# sum-mixer.net
KiCad netlist of a schematic drawn in EAGLE
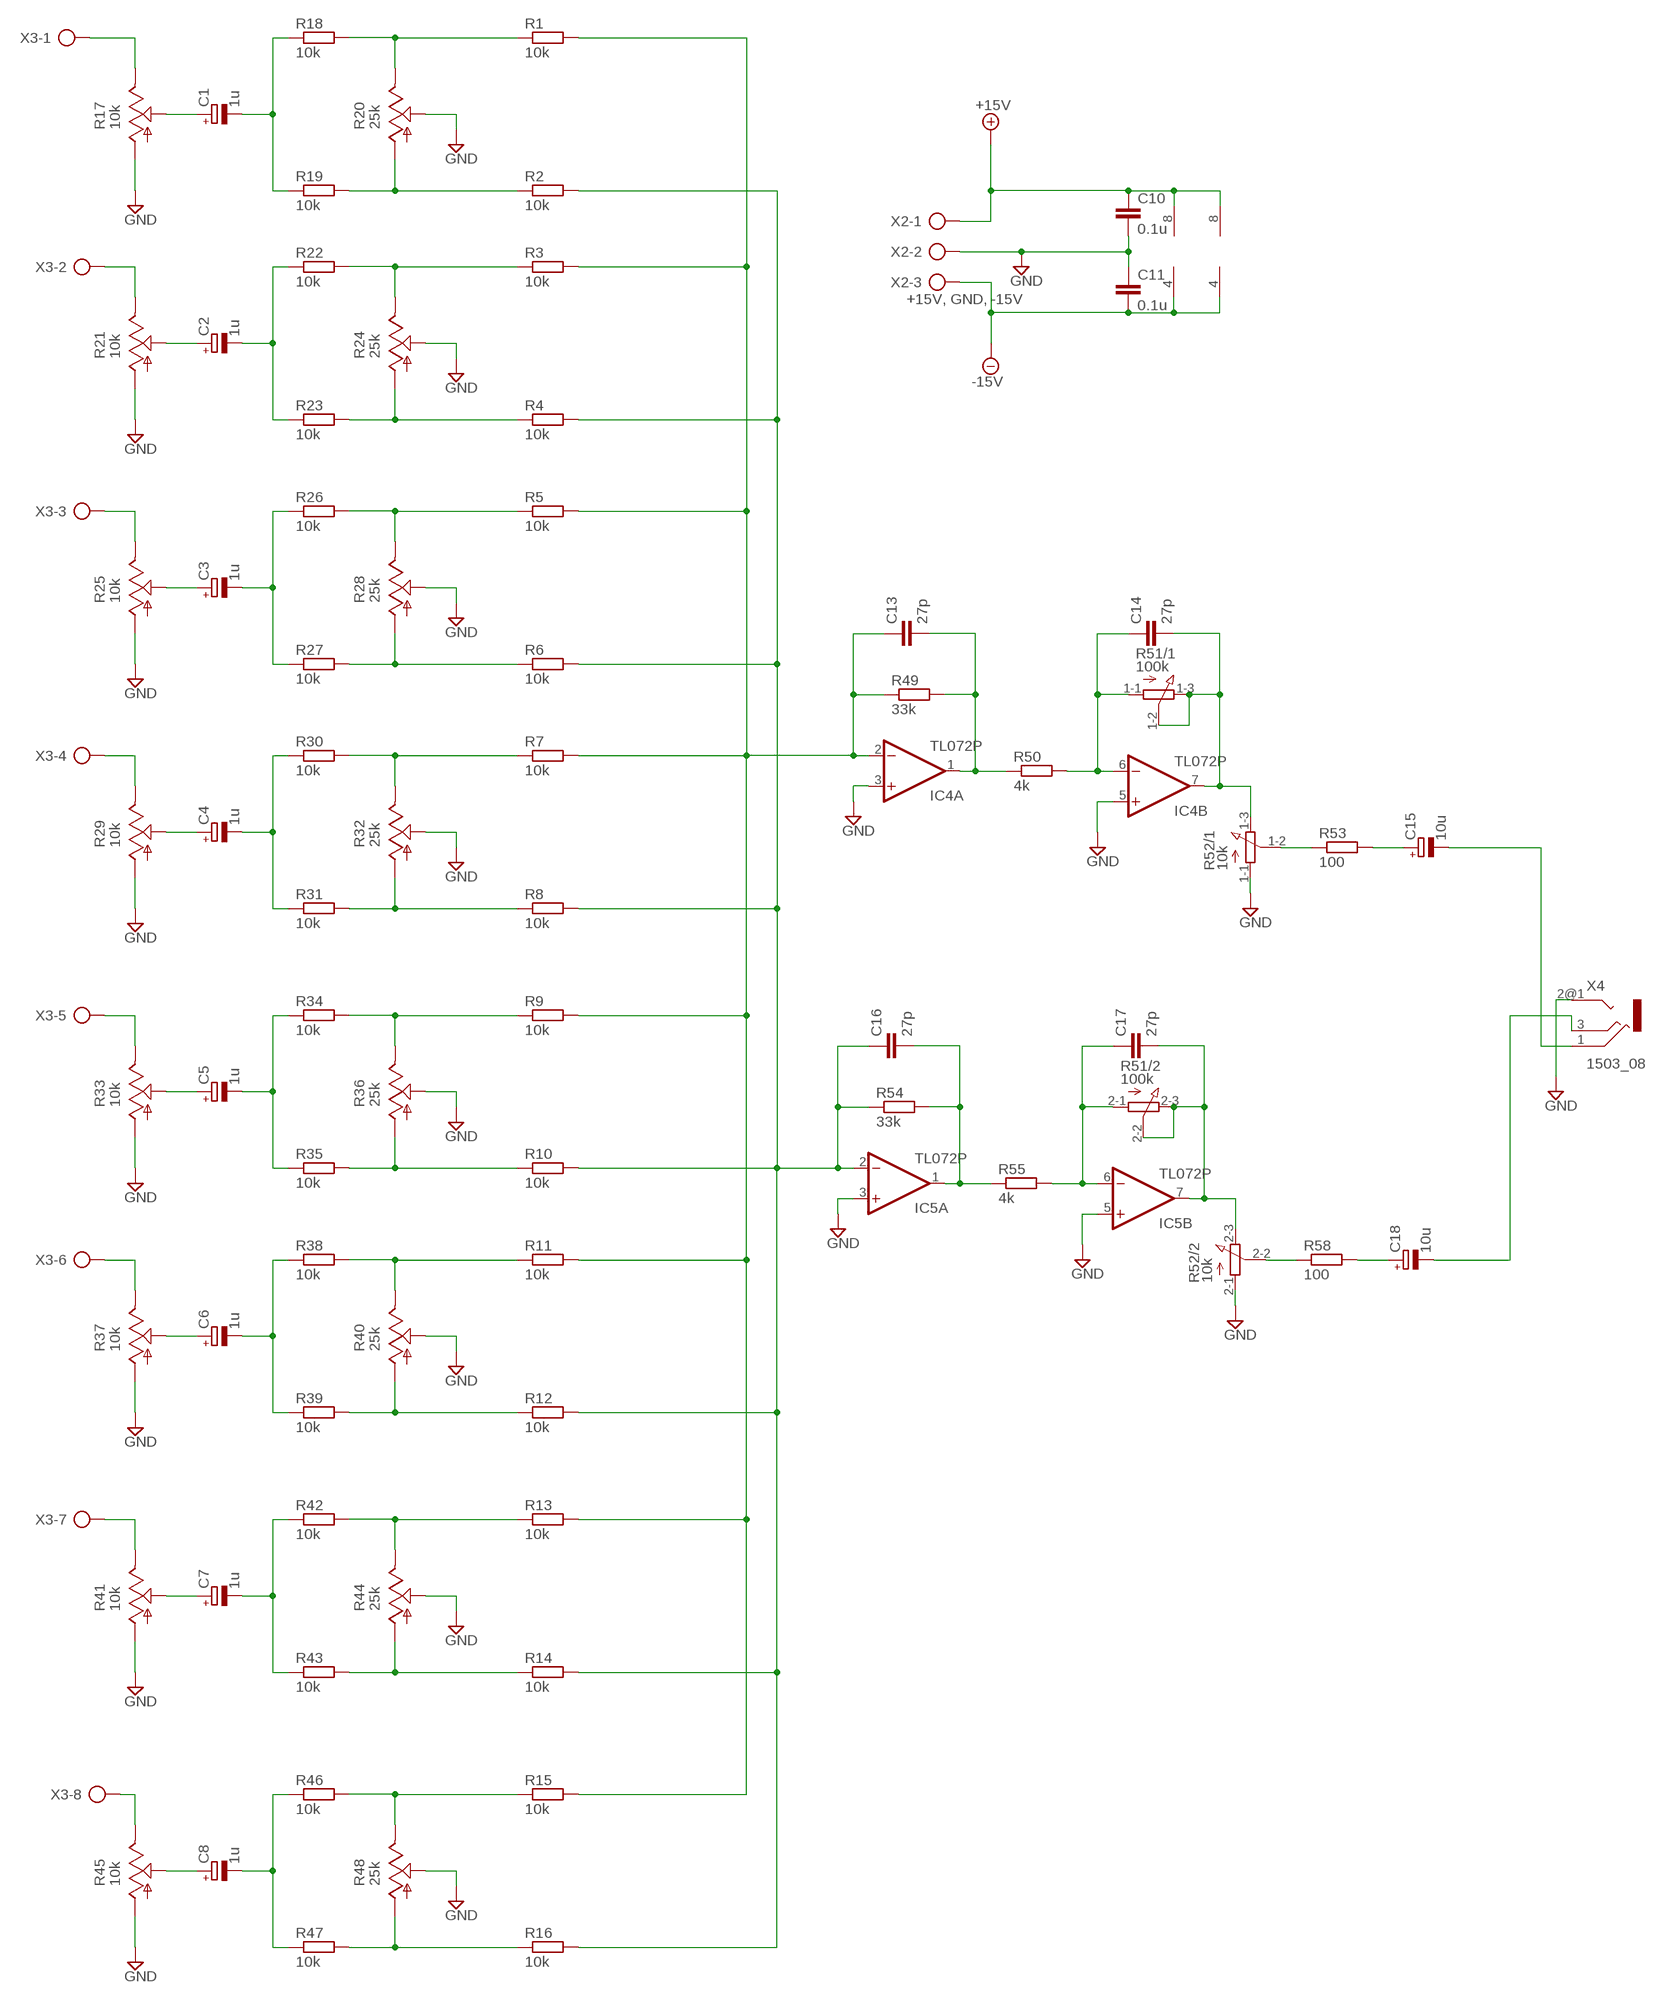
[diagram p0: schematic, sheet 1]

(export (version "E")
  (design (tool "Eeschema 10.0.6"))
  (components
    (comp (ref "C1")
      (value "1u")
      (footprint "eagle-import:E5-6")
      (libsource (lib "eagle-import") (part "CPOL-EUE5-6"))
    )
    (comp (ref "C2")
      (value "1u")
      (footprint "eagle-import:E5-6")
      (libsource (lib "eagle-import") (part "CPOL-EUE5-6"))
    )
    (comp (ref "C3")
      (value "1u")
      (footprint "eagle-import:E5-6")
      (libsource (lib "eagle-import") (part "CPOL-EUE5-6"))
    )
    (comp (ref "C4")
      (value "1u")
      (footprint "eagle-import:E5-6")
      (libsource (lib "eagle-import") (part "CPOL-EUE5-6"))
    )
    (comp (ref "C5")
      (value "1u")
      (footprint "eagle-import:E5-6")
      (libsource (lib "eagle-import") (part "CPOL-EUE5-6"))
    )
    (comp (ref "C6")
      (value "1u")
      (footprint "eagle-import:E5-6")
      (libsource (lib "eagle-import") (part "CPOL-EUE5-6"))
    )
    (comp (ref "C7")
      (value "1u")
      (footprint "eagle-import:E5-6")
      (libsource (lib "eagle-import") (part "CPOL-EUE5-6"))
    )
    (comp (ref "C8")
      (value "1u")
      (footprint "eagle-import:E5-6")
      (libsource (lib "eagle-import") (part "CPOL-EUE5-6"))
    )
    (comp (ref "C10")
      (value "0.1u")
      (footprint "eagle-import:C075-042X103")
      (libsource (lib "eagle-import") (part "C-EU075-042X103"))
    )
    (comp (ref "C11")
      (value "0.1u")
      (footprint "eagle-import:C075-042X103")
      (libsource (lib "eagle-import") (part "C-EU075-042X103"))
    )
    (comp (ref "C13")
      (value "27p")
      (footprint "eagle-import:C025-024X044")
      (libsource (lib "eagle-import") (part "C-EU025-024X044"))
    )
    (comp (ref "C14")
      (value "27p")
      (footprint "eagle-import:C025-024X044")
      (libsource (lib "eagle-import") (part "C-EU025-024X044"))
    )
    (comp (ref "C15")
      (value "10u")
      (footprint "eagle-import:E5-6")
      (libsource (lib "eagle-import") (part "CPOL-EUE5-6"))
    )
    (comp (ref "C16")
      (value "27p")
      (footprint "eagle-import:C025-024X044")
      (libsource (lib "eagle-import") (part "C-EU025-024X044"))
    )
    (comp (ref "C17")
      (value "27p")
      (footprint "eagle-import:C025-024X044")
      (libsource (lib "eagle-import") (part "C-EU025-024X044"))
    )
    (comp (ref "C18")
      (value "10u")
      (footprint "eagle-import:E5-6")
      (libsource (lib "eagle-import") (part "CPOL-EUE5-6"))
    )
    (comp (ref "IC4")
      (value "TL072P")
      (footprint "eagle-import:DIL08")
      (libsource (lib "eagle-import") (part "TL072P"))
    )
    (comp (ref "IC5")
      (value "TL072P")
      (footprint "eagle-import:DIL08")
      (libsource (lib "eagle-import") (part "TL072P"))
    )
    (comp (ref "R1")
      (value "10k")
      (footprint "eagle-import:0207_5V")
      (libsource (lib "eagle-import") (part "R-EU_0207/5V"))
    )
    (comp (ref "R2")
      (value "10k")
      (footprint "eagle-import:0207_5V")
      (libsource (lib "eagle-import") (part "R-EU_0207/5V"))
    )
    (comp (ref "R3")
      (value "10k")
      (footprint "eagle-import:0207_5V")
      (libsource (lib "eagle-import") (part "R-EU_0207/5V"))
    )
    (comp (ref "R4")
      (value "10k")
      (footprint "eagle-import:0207_5V")
      (libsource (lib "eagle-import") (part "R-EU_0207/5V"))
    )
    (comp (ref "R5")
      (value "10k")
      (footprint "eagle-import:0207_5V")
      (libsource (lib "eagle-import") (part "R-EU_0207/5V"))
    )
    (comp (ref "R6")
      (value "10k")
      (footprint "eagle-import:0207_5V")
      (libsource (lib "eagle-import") (part "R-EU_0207/5V"))
    )
    (comp (ref "R7")
      (value "10k")
      (footprint "eagle-import:0207_5V")
      (libsource (lib "eagle-import") (part "R-EU_0207/5V"))
    )
    (comp (ref "R8")
      (value "10k")
      (footprint "eagle-import:0207_5V")
      (libsource (lib "eagle-import") (part "R-EU_0207/5V"))
    )
    (comp (ref "R9")
      (value "10k")
      (footprint "eagle-import:0207_5V")
      (libsource (lib "eagle-import") (part "R-EU_0207/5V"))
    )
    (comp (ref "R10")
      (value "10k")
      (footprint "eagle-import:0207_5V")
      (libsource (lib "eagle-import") (part "R-EU_0207/5V"))
    )
    (comp (ref "R11")
      (value "10k")
      (footprint "eagle-import:0207_5V")
      (libsource (lib "eagle-import") (part "R-EU_0207/5V"))
    )
    (comp (ref "R12")
      (value "10k")
      (footprint "eagle-import:0207_5V")
      (libsource (lib "eagle-import") (part "R-EU_0207/5V"))
    )
    (comp (ref "R13")
      (value "10k")
      (footprint "eagle-import:0207_5V")
      (libsource (lib "eagle-import") (part "R-EU_0207/5V"))
    )
    (comp (ref "R14")
      (value "10k")
      (footprint "eagle-import:0207_5V")
      (libsource (lib "eagle-import") (part "R-EU_0207/5V"))
    )
    (comp (ref "R15")
      (value "10k")
      (footprint "eagle-import:0207_5V")
      (libsource (lib "eagle-import") (part "R-EU_0207/5V"))
    )
    (comp (ref "R16")
      (value "10k")
      (footprint "eagle-import:0207_5V")
      (libsource (lib "eagle-import") (part "R-EU_0207/5V"))
    )
    (comp (ref "R17")
      (value "10k")
      (footprint "eagle-import:B25P")
      (libsource (lib "eagle-import") (part "TRIM_US-B25P"))
    )
    (comp (ref "R18")
      (value "10k")
      (footprint "eagle-import:0207_5V")
      (libsource (lib "eagle-import") (part "R-EU_0207/5V"))
    )
    (comp (ref "R19")
      (value "10k")
      (footprint "eagle-import:0207_5V")
      (libsource (lib "eagle-import") (part "R-EU_0207/5V"))
    )
    (comp (ref "R20")
      (value "25k")
      (footprint "eagle-import:B25P")
      (libsource (lib "eagle-import") (part "TRIM_US-B25P"))
    )
    (comp (ref "R21")
      (value "10k")
      (footprint "eagle-import:B25P")
      (libsource (lib "eagle-import") (part "TRIM_US-B25P"))
    )
    (comp (ref "R22")
      (value "10k")
      (footprint "eagle-import:0207_5V")
      (libsource (lib "eagle-import") (part "R-EU_0207/5V"))
    )
    (comp (ref "R23")
      (value "10k")
      (footprint "eagle-import:0207_5V")
      (libsource (lib "eagle-import") (part "R-EU_0207/5V"))
    )
    (comp (ref "R24")
      (value "25k")
      (footprint "eagle-import:B25P")
      (libsource (lib "eagle-import") (part "TRIM_US-B25P"))
    )
    (comp (ref "R25")
      (value "10k")
      (footprint "eagle-import:B25P")
      (libsource (lib "eagle-import") (part "TRIM_US-B25P"))
    )
    (comp (ref "R26")
      (value "10k")
      (footprint "eagle-import:0207_5V")
      (libsource (lib "eagle-import") (part "R-EU_0207/5V"))
    )
    (comp (ref "R27")
      (value "10k")
      (footprint "eagle-import:0207_5V")
      (libsource (lib "eagle-import") (part "R-EU_0207/5V"))
    )
    (comp (ref "R28")
      (value "25k")
      (footprint "eagle-import:B25P")
      (libsource (lib "eagle-import") (part "TRIM_US-B25P"))
    )
    (comp (ref "R29")
      (value "10k")
      (footprint "eagle-import:B25P")
      (libsource (lib "eagle-import") (part "TRIM_US-B25P"))
    )
    (comp (ref "R30")
      (value "10k")
      (footprint "eagle-import:0207_5V")
      (libsource (lib "eagle-import") (part "R-EU_0207/5V"))
    )
    (comp (ref "R31")
      (value "10k")
      (footprint "eagle-import:0207_5V")
      (libsource (lib "eagle-import") (part "R-EU_0207/5V"))
    )
    (comp (ref "R32")
      (value "25k")
      (footprint "eagle-import:B25P")
      (libsource (lib "eagle-import") (part "TRIM_US-B25P"))
    )
    (comp (ref "R33")
      (value "10k")
      (footprint "eagle-import:B25P")
      (libsource (lib "eagle-import") (part "TRIM_US-B25P"))
    )
    (comp (ref "R34")
      (value "10k")
      (footprint "eagle-import:0207_5V")
      (libsource (lib "eagle-import") (part "R-EU_0207/5V"))
    )
    (comp (ref "R35")
      (value "10k")
      (footprint "eagle-import:0207_5V")
      (libsource (lib "eagle-import") (part "R-EU_0207/5V"))
    )
    (comp (ref "R36")
      (value "25k")
      (footprint "eagle-import:B25P")
      (libsource (lib "eagle-import") (part "TRIM_US-B25P"))
    )
    (comp (ref "R37")
      (value "10k")
      (footprint "eagle-import:B25P")
      (libsource (lib "eagle-import") (part "TRIM_US-B25P"))
    )
    (comp (ref "R38")
      (value "10k")
      (footprint "eagle-import:0207_5V")
      (libsource (lib "eagle-import") (part "R-EU_0207/5V"))
    )
    (comp (ref "R39")
      (value "10k")
      (footprint "eagle-import:0207_5V")
      (libsource (lib "eagle-import") (part "R-EU_0207/5V"))
    )
    (comp (ref "R40")
      (value "25k")
      (footprint "eagle-import:B25P")
      (libsource (lib "eagle-import") (part "TRIM_US-B25P"))
    )
    (comp (ref "R41")
      (value "10k")
      (footprint "eagle-import:B25P")
      (libsource (lib "eagle-import") (part "TRIM_US-B25P"))
    )
    (comp (ref "R42")
      (value "10k")
      (footprint "eagle-import:0207_5V")
      (libsource (lib "eagle-import") (part "R-EU_0207/5V"))
    )
    (comp (ref "R43")
      (value "10k")
      (footprint "eagle-import:0207_5V")
      (libsource (lib "eagle-import") (part "R-EU_0207/5V"))
    )
    (comp (ref "R44")
      (value "25k")
      (footprint "eagle-import:B25P")
      (libsource (lib "eagle-import") (part "TRIM_US-B25P"))
    )
    (comp (ref "R45")
      (value "10k")
      (footprint "eagle-import:B25P")
      (libsource (lib "eagle-import") (part "TRIM_US-B25P"))
    )
    (comp (ref "R46")
      (value "10k")
      (footprint "eagle-import:0207_5V")
      (libsource (lib "eagle-import") (part "R-EU_0207/5V"))
    )
    (comp (ref "R47")
      (value "10k")
      (footprint "eagle-import:0207_5V")
      (libsource (lib "eagle-import") (part "R-EU_0207/5V"))
    )
    (comp (ref "R48")
      (value "25k")
      (footprint "eagle-import:B25P")
      (libsource (lib "eagle-import") (part "TRIM_US-B25P"))
    )
    (comp (ref "R49")
      (value "33k")
      (footprint "eagle-import:0207_5V")
      (libsource (lib "eagle-import") (part "R-EU_0207/5V"))
    )
    (comp (ref "R50")
      (value "4k")
      (footprint "eagle-import:0207_5V")
      (libsource (lib "eagle-import") (part "R-EU_0207/5V"))
    )
    (comp (ref "R51")
      (value "100k")
      (footprint "eagle-import:3RP_1610G")
      (libsource (lib "eagle-import") (part "3RP/1610G"))
    )
    (comp (ref "R52")
      (value "10k")
      (footprint "eagle-import:3RP_1610G")
      (libsource (lib "eagle-import") (part "3RP/1610G"))
    )
    (comp (ref "R53")
      (value "100")
      (footprint "eagle-import:0207_5V")
      (libsource (lib "eagle-import") (part "R-EU_0207/5V"))
    )
    (comp (ref "R54")
      (value "33k")
      (footprint "eagle-import:0207_5V")
      (libsource (lib "eagle-import") (part "R-EU_0207/5V"))
    )
    (comp (ref "R55")
      (value "4k")
      (footprint "eagle-import:0207_5V")
      (libsource (lib "eagle-import") (part "R-EU_0207/5V"))
    )
    (comp (ref "R58")
      (value "100")
      (footprint "eagle-import:0207_5V")
      (libsource (lib "eagle-import") (part "R-EU_0207/5V"))
    )
    (comp (ref "X2")
      (value "+15V, GND, -15V")
      (footprint "eagle-import:AK300_3")
      (libsource (lib "eagle-import") (part "AK300/3"))
    )
    (comp (ref "X3")
      (value "AK300/8")
      (footprint "eagle-import:AK300_8")
      (libsource (lib "eagle-import") (part "AK300/8"))
    )
    (comp (ref "X4")
      (value "1503_08")
      (footprint "eagle-import:1503_08")
      (libsource (lib "eagle-import") (part "1503_?08"))
    )
  )
  (nets
    (net (code "1") (name "+15V") (class "Default")
      (node (ref "C10") (pin "1") (pinfunction "1_1") (pintype "passive"))
      (node (ref "IC4") (pin "8") (pinfunction "V+_8") (pintype "power_in"))
      (node (ref "IC5") (pin "8") (pinfunction "V+_8") (pintype "power_in"))
      (node (ref "X2") (pin "1") (pinfunction "KL_1") (pintype "passive"))
    )
    (net (code "2") (name "-15V") (class "Default")
      (node (ref "C11") (pin "2") (pinfunction "2_2") (pintype "passive"))
      (node (ref "IC4") (pin "4") (pinfunction "V-_4") (pintype "power_in"))
      (node (ref "IC5") (pin "4") (pinfunction "V-_4") (pintype "power_in"))
      (node (ref "X2") (pin "3") (pinfunction "KL_3") (pintype "passive"))
    )
    (net (code "3") (name "GND") (class "Default")
      (node (ref "C10") (pin "2") (pinfunction "2_2") (pintype "passive"))
      (node (ref "C11") (pin "1") (pinfunction "1_1") (pintype "passive"))
      (node (ref "IC4") (pin "3") (pinfunction "+IN_3") (pintype "input"))
      (node (ref "IC4") (pin "5") (pinfunction "+IN_5") (pintype "input"))
      (node (ref "IC5") (pin "3") (pinfunction "+IN_3") (pintype "input"))
      (node (ref "IC5") (pin "5") (pinfunction "+IN_5") (pintype "input"))
      (node (ref "R17") (pin "A") (pinfunction "A_A") (pintype "passive"))
      (node (ref "R20") (pin "S") (pinfunction "S_S") (pintype "passive"))
      (node (ref "R21") (pin "A") (pinfunction "A_A") (pintype "passive"))
      (node (ref "R24") (pin "S") (pinfunction "S_S") (pintype "passive"))
      (node (ref "R25") (pin "A") (pinfunction "A_A") (pintype "passive"))
      (node (ref "R28") (pin "S") (pinfunction "S_S") (pintype "passive"))
      (node (ref "R29") (pin "A") (pinfunction "A_A") (pintype "passive"))
      (node (ref "R32") (pin "S") (pinfunction "S_S") (pintype "passive"))
      (node (ref "R33") (pin "A") (pinfunction "A_A") (pintype "passive"))
      (node (ref "R36") (pin "S") (pinfunction "S_S") (pintype "passive"))
      (node (ref "R37") (pin "A") (pinfunction "A_A") (pintype "passive"))
      (node (ref "R40") (pin "S") (pinfunction "S_S") (pintype "passive"))
      (node (ref "R41") (pin "A") (pinfunction "A_A") (pintype "passive"))
      (node (ref "R44") (pin "S") (pinfunction "S_S") (pintype "passive"))
      (node (ref "R45") (pin "A") (pinfunction "A_A") (pintype "passive"))
      (node (ref "R48") (pin "S") (pinfunction "S_S") (pintype "passive"))
      (node (ref "R52") (pin "1-1") (pinfunction "A_1-1") (pintype "passive"))
      (node (ref "R52") (pin "2-1") (pinfunction "A_2-1") (pintype "passive"))
      (node (ref "X2") (pin "2") (pinfunction "KL_2") (pintype "passive"))
      (node (ref "X4") (pin "2@1") (pinfunction "2_2@1") (pintype "passive"))
    )
    (net (code "4") (name "Net-(C1-Pad+)") (class "Default")
      (node (ref "C1") (pin "+") (pinfunction "+_+") (pintype "passive"))
      (node (ref "R17") (pin "S") (pinfunction "S_S") (pintype "passive"))
    )
    (net (code "5") (name "Net-(C1-Pad-)") (class "Default")
      (node (ref "C1") (pin "-") (pinfunction "-_-") (pintype "passive"))
      (node (ref "R18") (pin "1") (pinfunction "1_1") (pintype "passive"))
      (node (ref "R19") (pin "1") (pinfunction "1_1") (pintype "passive"))
    )
    (net (code "6") (name "Net-(C2-Pad+)") (class "Default")
      (node (ref "C2") (pin "+") (pinfunction "+_+") (pintype "passive"))
      (node (ref "R21") (pin "S") (pinfunction "S_S") (pintype "passive"))
    )
    (net (code "7") (name "Net-(C2-Pad-)") (class "Default")
      (node (ref "C2") (pin "-") (pinfunction "-_-") (pintype "passive"))
      (node (ref "R22") (pin "1") (pinfunction "1_1") (pintype "passive"))
      (node (ref "R23") (pin "1") (pinfunction "1_1") (pintype "passive"))
    )
    (net (code "8") (name "Net-(C3-Pad+)") (class "Default")
      (node (ref "C3") (pin "+") (pinfunction "+_+") (pintype "passive"))
      (node (ref "R25") (pin "S") (pinfunction "S_S") (pintype "passive"))
    )
    (net (code "9") (name "Net-(C3-Pad-)") (class "Default")
      (node (ref "C3") (pin "-") (pinfunction "-_-") (pintype "passive"))
      (node (ref "R26") (pin "1") (pinfunction "1_1") (pintype "passive"))
      (node (ref "R27") (pin "1") (pinfunction "1_1") (pintype "passive"))
    )
    (net (code "10") (name "Net-(C4-Pad+)") (class "Default")
      (node (ref "C4") (pin "+") (pinfunction "+_+") (pintype "passive"))
      (node (ref "R29") (pin "S") (pinfunction "S_S") (pintype "passive"))
    )
    (net (code "11") (name "Net-(C4-Pad-)") (class "Default")
      (node (ref "C4") (pin "-") (pinfunction "-_-") (pintype "passive"))
      (node (ref "R30") (pin "1") (pinfunction "1_1") (pintype "passive"))
      (node (ref "R31") (pin "1") (pinfunction "1_1") (pintype "passive"))
    )
    (net (code "12") (name "Net-(C5-Pad+)") (class "Default")
      (node (ref "C5") (pin "+") (pinfunction "+_+") (pintype "passive"))
      (node (ref "R33") (pin "S") (pinfunction "S_S") (pintype "passive"))
    )
    (net (code "13") (name "Net-(C5-Pad-)") (class "Default")
      (node (ref "C5") (pin "-") (pinfunction "-_-") (pintype "passive"))
      (node (ref "R34") (pin "1") (pinfunction "1_1") (pintype "passive"))
      (node (ref "R35") (pin "1") (pinfunction "1_1") (pintype "passive"))
    )
    (net (code "14") (name "Net-(C6-Pad+)") (class "Default")
      (node (ref "C6") (pin "+") (pinfunction "+_+") (pintype "passive"))
      (node (ref "R37") (pin "S") (pinfunction "S_S") (pintype "passive"))
    )
    (net (code "15") (name "Net-(C6-Pad-)") (class "Default")
      (node (ref "C6") (pin "-") (pinfunction "-_-") (pintype "passive"))
      (node (ref "R38") (pin "1") (pinfunction "1_1") (pintype "passive"))
      (node (ref "R39") (pin "1") (pinfunction "1_1") (pintype "passive"))
    )
    (net (code "16") (name "Net-(C7-Pad+)") (class "Default")
      (node (ref "C7") (pin "+") (pinfunction "+_+") (pintype "passive"))
      (node (ref "R41") (pin "S") (pinfunction "S_S") (pintype "passive"))
    )
    (net (code "17") (name "Net-(C7-Pad-)") (class "Default")
      (node (ref "C7") (pin "-") (pinfunction "-_-") (pintype "passive"))
      (node (ref "R42") (pin "1") (pinfunction "1_1") (pintype "passive"))
      (node (ref "R43") (pin "1") (pinfunction "1_1") (pintype "passive"))
    )
    (net (code "18") (name "Net-(C8-Pad+)") (class "Default")
      (node (ref "C8") (pin "+") (pinfunction "+_+") (pintype "passive"))
      (node (ref "R45") (pin "S") (pinfunction "S_S") (pintype "passive"))
    )
    (net (code "19") (name "Net-(C8-Pad-)") (class "Default")
      (node (ref "C8") (pin "-") (pinfunction "-_-") (pintype "passive"))
      (node (ref "R46") (pin "1") (pinfunction "1_1") (pintype "passive"))
      (node (ref "R47") (pin "1") (pinfunction "1_1") (pintype "passive"))
    )
    (net (code "20") (name "Net-(C15-Pad+)") (class "Default")
      (node (ref "C15") (pin "+") (pinfunction "+_+") (pintype "passive"))
      (node (ref "R53") (pin "2") (pinfunction "2_2") (pintype "passive"))
    )
    (net (code "21") (name "Net-(C15-Pad-)") (class "Default")
      (node (ref "C15") (pin "-") (pinfunction "-_-") (pintype "passive"))
      (node (ref "X4") (pin "1") (pinfunction "1_1") (pintype "passive"))
    )
    (net (code "22") (name "Net-(C18-Pad+)") (class "Default")
      (node (ref "C18") (pin "+") (pinfunction "+_+") (pintype "passive"))
      (node (ref "R58") (pin "2") (pinfunction "2_2") (pintype "passive"))
    )
    (net (code "23") (name "Net-(C18-Pad-)") (class "Default")
      (node (ref "C18") (pin "-") (pinfunction "-_-") (pintype "passive"))
      (node (ref "X4") (pin "3") (pinfunction "3_3") (pintype "passive"))
    )
    (net (code "24") (name "Net-(IC4A--IN)") (class "Default")
      (node (ref "C13") (pin "1") (pinfunction "1_1") (pintype "passive"))
      (node (ref "IC4") (pin "2") (pinfunction "-IN_2") (pintype "input"))
      (node (ref "R1") (pin "2") (pinfunction "2_2") (pintype "passive"))
      (node (ref "R11") (pin "2") (pinfunction "2_2") (pintype "passive"))
      (node (ref "R13") (pin "2") (pinfunction "2_2") (pintype "passive"))
      (node (ref "R15") (pin "2") (pinfunction "2_2") (pintype "passive"))
      (node (ref "R3") (pin "2") (pinfunction "2_2") (pintype "passive"))
      (node (ref "R49") (pin "1") (pinfunction "1_1") (pintype "passive"))
      (node (ref "R5") (pin "2") (pinfunction "2_2") (pintype "passive"))
      (node (ref "R7") (pin "2") (pinfunction "2_2") (pintype "passive"))
      (node (ref "R9") (pin "2") (pinfunction "2_2") (pintype "passive"))
    )
    (net (code "25") (name "Net-(IC4A-OUT)") (class "Default")
      (node (ref "C13") (pin "2") (pinfunction "2_2") (pintype "passive"))
      (node (ref "IC4") (pin "1") (pinfunction "OUT_1") (pintype "output"))
      (node (ref "R49") (pin "2") (pinfunction "2_2") (pintype "passive"))
      (node (ref "R50") (pin "1") (pinfunction "1_1") (pintype "passive"))
    )
    (net (code "26") (name "Net-(IC4B--IN)") (class "Default")
      (node (ref "C14") (pin "1") (pinfunction "1_1") (pintype "passive"))
      (node (ref "IC4") (pin "6") (pinfunction "-IN_6") (pintype "input"))
      (node (ref "R50") (pin "2") (pinfunction "2_2") (pintype "passive"))
      (node (ref "R51") (pin "1-1") (pinfunction "A_1-1") (pintype "passive"))
    )
    (net (code "27") (name "Net-(IC4B-OUT)") (class "Default")
      (node (ref "C14") (pin "2") (pinfunction "2_2") (pintype "passive"))
      (node (ref "IC4") (pin "7") (pinfunction "OUT_7") (pintype "output"))
      (node (ref "R51") (pin "1-2") (pinfunction "S_1-2") (pintype "passive"))
      (node (ref "R51") (pin "1-3") (pinfunction "E_1-3") (pintype "passive"))
      (node (ref "R52") (pin "1-3") (pinfunction "E_1-3") (pintype "passive"))
    )
    (net (code "28") (name "Net-(IC5A--IN)") (class "Default")
      (node (ref "C16") (pin "1") (pinfunction "1_1") (pintype "passive"))
      (node (ref "IC5") (pin "2") (pinfunction "-IN_2") (pintype "input"))
      (node (ref "R10") (pin "2") (pinfunction "2_2") (pintype "passive"))
      (node (ref "R12") (pin "2") (pinfunction "2_2") (pintype "passive"))
      (node (ref "R14") (pin "2") (pinfunction "2_2") (pintype "passive"))
      (node (ref "R16") (pin "2") (pinfunction "2_2") (pintype "passive"))
      (node (ref "R2") (pin "2") (pinfunction "2_2") (pintype "passive"))
      (node (ref "R4") (pin "2") (pinfunction "2_2") (pintype "passive"))
      (node (ref "R54") (pin "1") (pinfunction "1_1") (pintype "passive"))
      (node (ref "R6") (pin "2") (pinfunction "2_2") (pintype "passive"))
      (node (ref "R8") (pin "2") (pinfunction "2_2") (pintype "passive"))
    )
    (net (code "29") (name "Net-(IC5A-OUT)") (class "Default")
      (node (ref "C16") (pin "2") (pinfunction "2_2") (pintype "passive"))
      (node (ref "IC5") (pin "1") (pinfunction "OUT_1") (pintype "output"))
      (node (ref "R54") (pin "2") (pinfunction "2_2") (pintype "passive"))
      (node (ref "R55") (pin "1") (pinfunction "1_1") (pintype "passive"))
    )
    (net (code "30") (name "Net-(IC5B--IN)") (class "Default")
      (node (ref "C17") (pin "1") (pinfunction "1_1") (pintype "passive"))
      (node (ref "IC5") (pin "6") (pinfunction "-IN_6") (pintype "input"))
      (node (ref "R51") (pin "2-1") (pinfunction "A_2-1") (pintype "passive"))
      (node (ref "R55") (pin "2") (pinfunction "2_2") (pintype "passive"))
    )
    (net (code "31") (name "Net-(IC5B-OUT)") (class "Default")
      (node (ref "C17") (pin "2") (pinfunction "2_2") (pintype "passive"))
      (node (ref "IC5") (pin "7") (pinfunction "OUT_7") (pintype "output"))
      (node (ref "R51") (pin "2-2") (pinfunction "S_2-2") (pintype "passive"))
      (node (ref "R51") (pin "2-3") (pinfunction "E_2-3") (pintype "passive"))
      (node (ref "R52") (pin "2-3") (pinfunction "E_2-3") (pintype "passive"))
    )
    (net (code "32") (name "Net-(R1-Pad1)") (class "Default")
      (node (ref "R1") (pin "1") (pinfunction "1_1") (pintype "passive"))
      (node (ref "R18") (pin "2") (pinfunction "2_2") (pintype "passive"))
      (node (ref "R20") (pin "E") (pinfunction "E_E") (pintype "passive"))
    )
    (net (code "33") (name "Net-(R10-Pad1)") (class "Default")
      (node (ref "R10") (pin "1") (pinfunction "1_1") (pintype "passive"))
      (node (ref "R35") (pin "2") (pinfunction "2_2") (pintype "passive"))
      (node (ref "R36") (pin "A") (pinfunction "A_A") (pintype "passive"))
    )
    (net (code "34") (name "Net-(R11-Pad1)") (class "Default")
      (node (ref "R11") (pin "1") (pinfunction "1_1") (pintype "passive"))
      (node (ref "R38") (pin "2") (pinfunction "2_2") (pintype "passive"))
      (node (ref "R40") (pin "E") (pinfunction "E_E") (pintype "passive"))
    )
    (net (code "35") (name "Net-(R12-Pad1)") (class "Default")
      (node (ref "R12") (pin "1") (pinfunction "1_1") (pintype "passive"))
      (node (ref "R39") (pin "2") (pinfunction "2_2") (pintype "passive"))
      (node (ref "R40") (pin "A") (pinfunction "A_A") (pintype "passive"))
    )
    (net (code "36") (name "Net-(R13-Pad1)") (class "Default")
      (node (ref "R13") (pin "1") (pinfunction "1_1") (pintype "passive"))
      (node (ref "R42") (pin "2") (pinfunction "2_2") (pintype "passive"))
      (node (ref "R44") (pin "E") (pinfunction "E_E") (pintype "passive"))
    )
    (net (code "37") (name "Net-(R14-Pad1)") (class "Default")
      (node (ref "R14") (pin "1") (pinfunction "1_1") (pintype "passive"))
      (node (ref "R43") (pin "2") (pinfunction "2_2") (pintype "passive"))
      (node (ref "R44") (pin "A") (pinfunction "A_A") (pintype "passive"))
    )
    (net (code "38") (name "Net-(R15-Pad1)") (class "Default")
      (node (ref "R15") (pin "1") (pinfunction "1_1") (pintype "passive"))
      (node (ref "R46") (pin "2") (pinfunction "2_2") (pintype "passive"))
      (node (ref "R48") (pin "E") (pinfunction "E_E") (pintype "passive"))
    )
    (net (code "39") (name "Net-(R16-Pad1)") (class "Default")
      (node (ref "R16") (pin "1") (pinfunction "1_1") (pintype "passive"))
      (node (ref "R47") (pin "2") (pinfunction "2_2") (pintype "passive"))
      (node (ref "R48") (pin "A") (pinfunction "A_A") (pintype "passive"))
    )
    (net (code "40") (name "Net-(R19-Pad2)") (class "Default")
      (node (ref "R19") (pin "2") (pinfunction "2_2") (pintype "passive"))
      (node (ref "R2") (pin "1") (pinfunction "1_1") (pintype "passive"))
      (node (ref "R20") (pin "A") (pinfunction "A_A") (pintype "passive"))
    )
    (net (code "41") (name "Net-(R22-Pad2)") (class "Default")
      (node (ref "R22") (pin "2") (pinfunction "2_2") (pintype "passive"))
      (node (ref "R24") (pin "E") (pinfunction "E_E") (pintype "passive"))
      (node (ref "R3") (pin "1") (pinfunction "1_1") (pintype "passive"))
    )
    (net (code "42") (name "Net-(R23-Pad2)") (class "Default")
      (node (ref "R23") (pin "2") (pinfunction "2_2") (pintype "passive"))
      (node (ref "R24") (pin "A") (pinfunction "A_A") (pintype "passive"))
      (node (ref "R4") (pin "1") (pinfunction "1_1") (pintype "passive"))
    )
    (net (code "43") (name "Net-(R26-Pad2)") (class "Default")
      (node (ref "R26") (pin "2") (pinfunction "2_2") (pintype "passive"))
      (node (ref "R28") (pin "E") (pinfunction "E_E") (pintype "passive"))
      (node (ref "R5") (pin "1") (pinfunction "1_1") (pintype "passive"))
    )
    (net (code "44") (name "Net-(R27-Pad2)") (class "Default")
      (node (ref "R27") (pin "2") (pinfunction "2_2") (pintype "passive"))
      (node (ref "R28") (pin "A") (pinfunction "A_A") (pintype "passive"))
      (node (ref "R6") (pin "1") (pinfunction "1_1") (pintype "passive"))
    )
    (net (code "45") (name "Net-(R30-Pad2)") (class "Default")
      (node (ref "R30") (pin "2") (pinfunction "2_2") (pintype "passive"))
      (node (ref "R32") (pin "E") (pinfunction "E_E") (pintype "passive"))
      (node (ref "R7") (pin "1") (pinfunction "1_1") (pintype "passive"))
    )
    (net (code "46") (name "Net-(R31-Pad2)") (class "Default")
      (node (ref "R31") (pin "2") (pinfunction "2_2") (pintype "passive"))
      (node (ref "R32") (pin "A") (pinfunction "A_A") (pintype "passive"))
      (node (ref "R8") (pin "1") (pinfunction "1_1") (pintype "passive"))
    )
    (net (code "47") (name "Net-(R34-Pad2)") (class "Default")
      (node (ref "R34") (pin "2") (pinfunction "2_2") (pintype "passive"))
      (node (ref "R36") (pin "E") (pinfunction "E_E") (pintype "passive"))
      (node (ref "R9") (pin "1") (pinfunction "1_1") (pintype "passive"))
    )
    (net (code "48") (name "Net-(R52A-S)") (class "Default")
      (node (ref "R52") (pin "1-2") (pinfunction "S_1-2") (pintype "passive"))
      (node (ref "R53") (pin "1") (pinfunction "1_1") (pintype "passive"))
    )
    (net (code "49") (name "Net-(R52B-S)") (class "Default")
      (node (ref "R52") (pin "2-2") (pinfunction "S_2-2") (pintype "passive"))
      (node (ref "R58") (pin "1") (pinfunction "1_1") (pintype "passive"))
    )
    (net (code "50") (name "Net-(X3A-KL)") (class "Default")
      (node (ref "R17") (pin "E") (pinfunction "E_E") (pintype "passive"))
      (node (ref "X3") (pin "1") (pinfunction "KL_1") (pintype "passive"))
    )
    (net (code "51") (name "Net-(X3B-KL)") (class "Default")
      (node (ref "R21") (pin "E") (pinfunction "E_E") (pintype "passive"))
      (node (ref "X3") (pin "2") (pinfunction "KL_2") (pintype "passive"))
    )
    (net (code "52") (name "Net-(X3C-KL)") (class "Default")
      (node (ref "R25") (pin "E") (pinfunction "E_E") (pintype "passive"))
      (node (ref "X3") (pin "3") (pinfunction "KL_3") (pintype "passive"))
    )
    (net (code "53") (name "Net-(X3D-KL)") (class "Default")
      (node (ref "R29") (pin "E") (pinfunction "E_E") (pintype "passive"))
      (node (ref "X3") (pin "4") (pinfunction "KL_4") (pintype "passive"))
    )
    (net (code "54") (name "Net-(X3E-KL)") (class "Default")
      (node (ref "R33") (pin "E") (pinfunction "E_E") (pintype "passive"))
      (node (ref "X3") (pin "5") (pinfunction "KL_5") (pintype "passive"))
    )
    (net (code "55") (name "Net-(X3F-KL)") (class "Default")
      (node (ref "R37") (pin "E") (pinfunction "E_E") (pintype "passive"))
      (node (ref "X3") (pin "6") (pinfunction "KL_6") (pintype "passive"))
    )
    (net (code "56") (name "Net-(X3G-KL)") (class "Default")
      (node (ref "R41") (pin "E") (pinfunction "E_E") (pintype "passive"))
      (node (ref "X3") (pin "7") (pinfunction "KL_7") (pintype "passive"))
    )
    (net (code "57") (name "Net-(X3H-KL)") (class "Default")
      (node (ref "R45") (pin "E") (pinfunction "E_E") (pintype "passive"))
      (node (ref "X3") (pin "8") (pinfunction "KL_8") (pintype "passive"))
    )
    (net (code "58") (name "unconnected-(X4-2-Pad2@2)") (class "Default")
      (node (ref "X4") (pin "2@2") (pinfunction "2_2@2") (pintype "passive"))
    )
  )
)
